# ptvo_fs.net
KiCad netlist of a schematic drawn in EAGLE
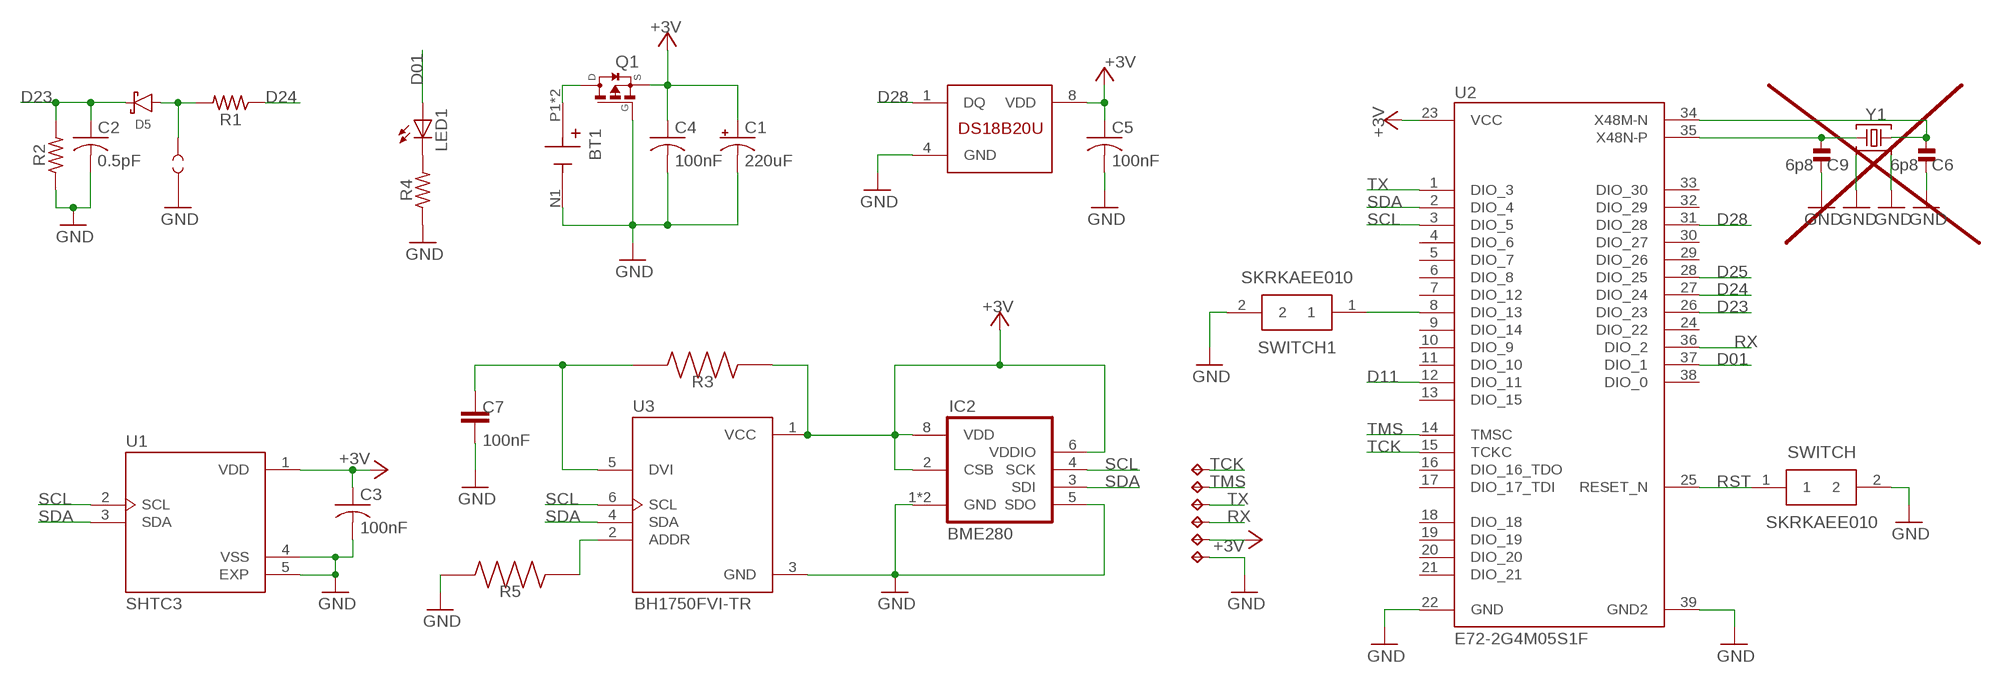
[diagram p0: schematic, sheet 1]

(export (version "E")
  (design (tool "Eeschema 10.0.6"))
  (components
    (comp (ref "BT1")
      (value "BAT-HLD-001")
      (footprint "eagle-import:BAT_BAT-HLD-001")
      (libsource (lib "eagle-import") (part "BAT-HLD-001"))
    )
    (comp (ref "C1")
      (value "220uF")
      (footprint "eagle-import:EIA7343")
      (libsource (lib "eagle-import") (part "100UF-POLAR-EIA7343-10V-10%(TANT)"))
    )
    (comp (ref "C2")
      (value "0.5pF")
      (footprint "eagle-import:C0805")
      (libsource (lib "eagle-import") (part "C-USC0805"))
    )
    (comp (ref "C3")
      (value "100nF")
      (footprint "eagle-import:C0805")
      (libsource (lib "eagle-import") (part "C-USC0805"))
    )
    (comp (ref "C4")
      (value "100nF")
      (footprint "eagle-import:C0805")
      (libsource (lib "eagle-import") (part "C-USC0805"))
    )
    (comp (ref "C5")
      (value "100nF")
      (footprint "eagle-import:C0805")
      (libsource (lib "eagle-import") (part "C-USC0805"))
    )
    (comp (ref "C6")
      (value "6p8")
      (footprint "eagle-import:_PKG_C_0402")
      (libsource (lib "eagle-import") (part "CAP-0402"))
    )
    (comp (ref "C7")
      (value "100nF")
      (footprint "eagle-import:CAPC1005X40N")
      (fields (field (name "MF") "Yageo") (field (name "MP") "RC0402FR-073M6L"))
      (libsource (lib "eagle-import") (part "CAP0402"))
    )
    (comp (ref "C9")
      (value "6p8")
      (footprint "eagle-import:_PKG_C_0402")
      (libsource (lib "eagle-import") (part "CAP-0402"))
    )
    (comp (ref "D5")
      (value "1N4148WS")
      (footprint "eagle-import:SOD-323")
      (libsource (lib "eagle-import") (part "DIODE-SCHOTTKY"))
    )
    (comp (ref "IC1")
      (value "DS18S20USOP8")
      (footprint "eagle-import:UMAX8")
      (libsource (lib "eagle-import") (part "DS18S20USOP8"))
    )
    (comp (ref "IC2")
      (value "BME280")
      (footprint "eagle-import:BME280")
      (libsource (lib "eagle-import") (part "BME280"))
    )
    (comp (ref "LED1")
      (value "LEDCHIP-LED0805")
      (footprint "eagle-import:CHIP-LED0805")
      (libsource (lib "eagle-import") (part "LEDCHIP-LED0805"))
    )
    (comp (ref "Q1")
      (value "SI2323DS")
      (footprint "eagle-import:SOT23")
      (fields (field (name "MF") "Vishay Siliconix"))
      (libsource (lib "eagle-import") (part "SI2323DS"))
    )
    (comp (ref "R1")
      (value "10k")
      (footprint "eagle-import:M0805")
      (libsource (lib "eagle-import") (part "R-US_M0805"))
    )
    (comp (ref "R2")
      (value "1M")
      (footprint "eagle-import:M0805")
      (libsource (lib "eagle-import") (part "R-US_M0805"))
    )
    (comp (ref "R3")
      (value "4.7k")
      (footprint "eagle-import:RESC1005X40N")
      (fields (field (name "MF") "Yageo") (field (name "MP") "RC0402FR-073M6L"))
      (libsource (lib "eagle-import") (part "RC0402FR-073M6L"))
    )
    (comp (ref "R4")
      (value "2.2k")
      (footprint "eagle-import:M0805")
      (libsource (lib "eagle-import") (part "R-US_M0805"))
    )
    (comp (ref "R5")
      (value "4.7k")
      (footprint "eagle-import:RESC1005X40N")
      (fields (field (name "MF") "Yageo") (field (name "MP") "RC0402FR-073M6L"))
      (libsource (lib "eagle-import") (part "RC0402FR-073M6L"))
    )
    (comp (ref "SWITCH")
      (value "SKRKAEE010")
      (footprint "eagle-import:SKRK")
      (fields (field (name "MF") "ALPS"))
      (libsource (lib "eagle-import") (part "SKRKAEE010"))
    )
    (comp (ref "SWITCH1")
      (value "SKRKAEE010")
      (footprint "eagle-import:SKRK")
      (fields (field (name "MF") "ALPS"))
      (libsource (lib "eagle-import") (part "SKRKAEE010"))
    )
    (comp (ref "TP1")
      (value "TEST-POINT2")
      (footprint "eagle-import:PAD.02X.02")
      (libsource (lib "eagle-import") (part "TEST-POINT2"))
    )
    (comp (ref "TP2")
      (value "TEST-POINT2")
      (footprint "eagle-import:PAD.02X.02")
      (libsource (lib "eagle-import") (part "TEST-POINT2"))
    )
    (comp (ref "TP3")
      (value "TPB1,27")
      (footprint "eagle-import:B1,27")
      (libsource (lib "eagle-import") (part "TPB1,27"))
    )
    (comp (ref "TP4")
      (value "TPB1,27")
      (footprint "eagle-import:B1,27")
      (libsource (lib "eagle-import") (part "TPB1,27"))
    )
    (comp (ref "TP5")
      (value "TPB1,27")
      (footprint "eagle-import:B1,27")
      (libsource (lib "eagle-import") (part "TPB1,27"))
    )
    (comp (ref "TP6")
      (value "TPB1,27")
      (footprint "eagle-import:B1,27")
      (libsource (lib "eagle-import") (part "TPB1,27"))
    )
    (comp (ref "TP7")
      (value "TPB1,27")
      (footprint "eagle-import:B1,27")
      (libsource (lib "eagle-import") (part "TPB1,27"))
    )
    (comp (ref "TP8")
      (value "TPB1,27")
      (footprint "eagle-import:B1,27")
      (libsource (lib "eagle-import") (part "TPB1,27"))
    )
    (comp (ref "U1")
      (value "SHTC3")
      (footprint "eagle-import:SON100P200X200X80-5N")
      (fields (field (name "MF") "Sensirion AG"))
      (libsource (lib "eagle-import") (part "SHTC3"))
    )
    (comp (ref "U2")
      (value "E72-2G4M05S1F")
      (footprint "eagle-import:E72-2G4M05S1F")
      (libsource (lib "eagle-import") (part "E72-2G4M05S1F"))
    )
    (comp (ref "U3")
      (value "BH1750FVI-TR")
      (footprint "eagle-import:XDCR_BH1750FVI-TR")
      (fields (field (name "MF") "Rohm"))
      (libsource (lib "eagle-import") (part "BH1750FVI-TR"))
    )
    (comp (ref "Y1")
      (value "Q22FA12800150")
      (footprint "eagle-import:XTAL-4P-2016")
      (fields (field (name "DIGIKEY_PART") "1253-2042-1-ND") (field (name "MFG_PART") "CX2016DB48000C0FPLC1"))
      (libsource (lib "eagle-import") (part "48.000MHZ_CX2016DB48000C0FPLC1"))
    )
  )
  (nets
    (net (code "1") (name "+3V") (class "Default")
      (node (ref "C1") (pin "A") (pinfunction "+_A") (pintype "passive"))
      (node (ref "C3") (pin "1") (pinfunction "1_1") (pintype "passive"))
      (node (ref "C4") (pin "1") (pinfunction "1_1") (pintype "passive"))
      (node (ref "C5") (pin "1") (pinfunction "1_1") (pintype "passive"))
      (node (ref "IC1") (pin "8") (pinfunction "VDD_8") (pintype "power_in"))
      (node (ref "IC2") (pin "2") (pinfunction "CSB_2") (pintype "input"))
      (node (ref "IC2") (pin "6") (pinfunction "VDDIO_6") (pintype "power_in"))
      (node (ref "IC2") (pin "8") (pinfunction "VDD_8") (pintype "power_in"))
      (node (ref "Q1") (pin "2") (pinfunction "S_2") (pintype "passive"))
      (node (ref "R3") (pin "1") (pinfunction "1_1") (pintype "passive"))
      (node (ref "TP6") (pin "TP") (pinfunction "TP_TP") (pintype "input"))
      (node (ref "U1") (pin "1") (pinfunction "VDD_1") (pintype "power_in"))
      (node (ref "U2") (pin "23") (pinfunction "VCC_23") (pintype "bidirectional"))
      (node (ref "U3") (pin "1") (pinfunction "VCC_1") (pintype "power_in"))
    )
    (net (code "2") (name "/D01") (class "Default")
      (node (ref "LED1") (pin "A") (pinfunction "A_A") (pintype "passive"))
      (node (ref "U2") (pin "37") (pinfunction "DIO_1_37") (pintype "bidirectional"))
    )
    (net (code "3") (name "/D11") (class "Default")
      (node (ref "U2") (pin "12") (pinfunction "DIO_11_12") (pintype "bidirectional"))
    )
    (net (code "4") (name "/D23") (class "Default")
      (node (ref "C2") (pin "1") (pinfunction "1_1") (pintype "passive"))
      (node (ref "D5") (pin "C") (pinfunction "C_C") (pintype "passive"))
      (node (ref "R2") (pin "2") (pinfunction "2_2") (pintype "passive"))
      (node (ref "U2") (pin "26") (pinfunction "DIO_23_26") (pintype "bidirectional"))
    )
    (net (code "5") (name "/D24") (class "Default")
      (node (ref "R1") (pin "1") (pinfunction "1_1") (pintype "passive"))
      (node (ref "U2") (pin "27") (pinfunction "DIO_24_27") (pintype "bidirectional"))
    )
    (net (code "6") (name "/D25") (class "Default")
      (node (ref "U2") (pin "28") (pinfunction "DIO_25_28") (pintype "bidirectional"))
    )
    (net (code "7") (name "/D28") (class "Default")
      (node (ref "IC1") (pin "1") (pinfunction "DQ_1") (pintype "bidirectional"))
      (node (ref "U2") (pin "31") (pinfunction "DIO_28_31") (pintype "bidirectional"))
    )
    (net (code "8") (name "/RST") (class "Default")
      (node (ref "SWITCH") (pin "1") (pinfunction "1_1") (pintype "passive"))
      (node (ref "U2") (pin "25") (pinfunction "RESET_N_25") (pintype "bidirectional"))
    )
    (net (code "9") (name "/RX") (class "Default")
      (node (ref "TP5") (pin "TP") (pinfunction "TP_TP") (pintype "input"))
      (node (ref "U2") (pin "36") (pinfunction "DIO_2_36") (pintype "bidirectional"))
    )
    (net (code "10") (name "/SCL") (class "Default")
      (node (ref "IC2") (pin "4") (pinfunction "SCK_4") (pintype "bidirectional"))
      (node (ref "U1") (pin "2") (pinfunction "SCL_2") (pintype "bidirectional"))
      (node (ref "U2") (pin "3") (pinfunction "DIO_5_3") (pintype "bidirectional"))
      (node (ref "U3") (pin "6") (pinfunction "SCL_6") (pintype "input"))
    )
    (net (code "11") (name "/SDA") (class "Default")
      (node (ref "IC2") (pin "3") (pinfunction "SDI_3") (pintype "bidirectional"))
      (node (ref "U1") (pin "3") (pinfunction "SDA_3") (pintype "bidirectional"))
      (node (ref "U2") (pin "2") (pinfunction "DIO_4_2") (pintype "bidirectional"))
      (node (ref "U3") (pin "4") (pinfunction "SDA_4") (pintype "bidirectional"))
    )
    (net (code "12") (name "/TCK") (class "Default")
      (node (ref "TP8") (pin "TP") (pinfunction "TP_TP") (pintype "input"))
      (node (ref "U2") (pin "15") (pinfunction "TCKC_15") (pintype "bidirectional"))
    )
    (net (code "13") (name "/TMS") (class "Default")
      (node (ref "TP3") (pin "TP") (pinfunction "TP_TP") (pintype "input"))
      (node (ref "U2") (pin "14") (pinfunction "TMSC_14") (pintype "bidirectional"))
    )
    (net (code "14") (name "/TX") (class "Default")
      (node (ref "TP4") (pin "TP") (pinfunction "TP_TP") (pintype "input"))
      (node (ref "U2") (pin "1") (pinfunction "DIO_3_1") (pintype "bidirectional"))
    )
    (net (code "15") (name "GND") (class "Default")
      (node (ref "BT1") (pin "N1") (pinfunction "-_N1") (pintype "passive"))
      (node (ref "C1") (pin "C") (pinfunction "-_C") (pintype "passive"))
      (node (ref "C2") (pin "2") (pinfunction "2_2") (pintype "passive"))
      (node (ref "C3") (pin "2") (pinfunction "2_2") (pintype "passive"))
      (node (ref "C4") (pin "2") (pinfunction "2_2") (pintype "passive"))
      (node (ref "C5") (pin "2") (pinfunction "2_2") (pintype "passive"))
      (node (ref "C6") (pin "1") (pinfunction "1_1") (pintype "passive"))
      (node (ref "C7") (pin "2") (pinfunction "2_2") (pintype "passive"))
      (node (ref "C9") (pin "1") (pinfunction "1_1") (pintype "passive"))
      (node (ref "IC1") (pin "4") (pinfunction "GND_4") (pintype "power_in"))
      (node (ref "IC2") (pin "1") (pinfunction "GND_1") (pintype "power_in"))
      (node (ref "IC2") (pin "5") (pinfunction "SDO_5") (pintype "input"))
      (node (ref "IC2") (pin "7") (pinfunction "GND_7") (pintype "power_in"))
      (node (ref "Q1") (pin "1") (pinfunction "G_1") (pintype "passive"))
      (node (ref "R2") (pin "1") (pinfunction "1_1") (pintype "passive"))
      (node (ref "R4") (pin "1") (pinfunction "1_1") (pintype "passive"))
      (node (ref "R5") (pin "2") (pinfunction "2_2") (pintype "passive"))
      (node (ref "SWITCH") (pin "2") (pinfunction "2_2") (pintype "passive"))
      (node (ref "SWITCH1") (pin "2") (pinfunction "2_2") (pintype "passive"))
      (node (ref "TP2") (pin "P$1") (pinfunction "1_P$1") (pintype "bidirectional"))
      (node (ref "TP7") (pin "TP") (pinfunction "TP_TP") (pintype "input"))
      (node (ref "U1") (pin "4") (pinfunction "VSS_4") (pintype "power_in"))
      (node (ref "U1") (pin "5") (pinfunction "EXP_5") (pintype "power_in"))
      (node (ref "U2") (pin "22") (pinfunction "GND_22") (pintype "bidirectional"))
      (node (ref "U2") (pin "39") (pinfunction "GND2_39") (pintype "bidirectional"))
      (node (ref "U3") (pin "3") (pinfunction "GND_3") (pintype "power_in"))
      (node (ref "Y1") (pin "2") (pinfunction "2_2") (pintype "bidirectional"))
      (node (ref "Y1") (pin "4") (pinfunction "4_4") (pintype "bidirectional"))
    )
    (net (code "16") (name "Net-(LED1-PadC)") (class "Default")
      (node (ref "LED1") (pin "C") (pinfunction "C_C") (pintype "passive"))
      (node (ref "R4") (pin "2") (pinfunction "2_2") (pintype "passive"))
    )
    (net (code "17") (name "Net-(Q1-D)") (class "Default")
      (node (ref "BT1") (pin "P1") (pinfunction "+_P1") (pintype "passive"))
      (node (ref "BT1") (pin "P2") (pinfunction "+_P2") (pintype "passive"))
      (node (ref "Q1") (pin "3") (pinfunction "D_3") (pintype "passive"))
    )
    (net (code "18") (name "Net-(TP1-1)") (class "Default")
      (node (ref "D5") (pin "A") (pinfunction "A_A") (pintype "passive"))
      (node (ref "R1") (pin "2") (pinfunction "2_2") (pintype "passive"))
      (node (ref "TP1") (pin "P$1") (pinfunction "1_P$1") (pintype "bidirectional"))
    )
    (net (code "19") (name "Net-(U2-DIO_13)") (class "Default")
      (node (ref "SWITCH1") (pin "1") (pinfunction "1_1") (pintype "passive"))
      (node (ref "U2") (pin "8") (pinfunction "DIO_13_8") (pintype "bidirectional"))
    )
    (net (code "20") (name "Net-(U2-X48M-N)") (class "Default")
      (node (ref "C6") (pin "2") (pinfunction "2_2") (pintype "passive"))
      (node (ref "U2") (pin "34") (pinfunction "X48M-N_34") (pintype "bidirectional"))
      (node (ref "Y1") (pin "3") (pinfunction "3_3") (pintype "passive"))
    )
    (net (code "21") (name "Net-(U2-X48N-P)") (class "Default")
      (node (ref "C9") (pin "2") (pinfunction "2_2") (pintype "passive"))
      (node (ref "U2") (pin "35") (pinfunction "X48N-P_35") (pintype "bidirectional"))
      (node (ref "Y1") (pin "1") (pinfunction "1_1") (pintype "passive"))
    )
    (net (code "22") (name "Net-(U3-ADDR)") (class "Default")
      (node (ref "R5") (pin "1") (pinfunction "1_1") (pintype "passive"))
      (node (ref "U3") (pin "2") (pinfunction "ADDR_2") (pintype "input"))
    )
    (net (code "23") (name "Net-(U3-DVI)") (class "Default")
      (node (ref "C7") (pin "1") (pinfunction "1_1") (pintype "passive"))
      (node (ref "R3") (pin "2") (pinfunction "2_2") (pintype "passive"))
      (node (ref "U3") (pin "5") (pinfunction "DVI_5") (pintype "input"))
    )
    (net (code "24") (name "unconnected-(U2-DIO_0-Pad38)") (class "Default")
      (node (ref "U2") (pin "38") (pinfunction "DIO_0_38") (pintype "bidirectional"))
    )
    (net (code "25") (name "unconnected-(U2-DIO_6-Pad4)") (class "Default")
      (node (ref "U2") (pin "4") (pinfunction "DIO_6_4") (pintype "bidirectional"))
    )
    (net (code "26") (name "unconnected-(U2-DIO_7-Pad5)") (class "Default")
      (node (ref "U2") (pin "5") (pinfunction "DIO_7_5") (pintype "bidirectional"))
    )
    (net (code "27") (name "unconnected-(U2-DIO_8-Pad6)") (class "Default")
      (node (ref "U2") (pin "6") (pinfunction "DIO_8_6") (pintype "bidirectional"))
    )
    (net (code "28") (name "unconnected-(U2-DIO_9-Pad10)") (class "Default")
      (node (ref "U2") (pin "10") (pinfunction "DIO_9_10") (pintype "bidirectional"))
    )
    (net (code "29") (name "unconnected-(U2-DIO_10-Pad11)") (class "Default")
      (node (ref "U2") (pin "11") (pinfunction "DIO_10_11") (pintype "bidirectional"))
    )
    (net (code "30") (name "unconnected-(U2-DIO_12-Pad7)") (class "Default")
      (node (ref "U2") (pin "7") (pinfunction "DIO_12_7") (pintype "bidirectional"))
    )
    (net (code "31") (name "unconnected-(U2-DIO_14-Pad9)") (class "Default")
      (node (ref "U2") (pin "9") (pinfunction "DIO_14_9") (pintype "bidirectional"))
    )
    (net (code "32") (name "unconnected-(U2-DIO_15-Pad13)") (class "Default")
      (node (ref "U2") (pin "13") (pinfunction "DIO_15_13") (pintype "bidirectional"))
    )
    (net (code "33") (name "unconnected-(U2-DIO_16_TDO-Pad16)") (class "Default")
      (node (ref "U2") (pin "16") (pinfunction "DIO_16_TDO_16") (pintype "bidirectional"))
    )
    (net (code "34") (name "unconnected-(U2-DIO_17_TDI-Pad17)") (class "Default")
      (node (ref "U2") (pin "17") (pinfunction "DIO_17_TDI_17") (pintype "bidirectional"))
    )
    (net (code "35") (name "unconnected-(U2-DIO_18-Pad18)") (class "Default")
      (node (ref "U2") (pin "18") (pinfunction "DIO_18_18") (pintype "bidirectional"))
    )
    (net (code "36") (name "unconnected-(U2-DIO_19-Pad19)") (class "Default")
      (node (ref "U2") (pin "19") (pinfunction "DIO_19_19") (pintype "bidirectional"))
    )
    (net (code "37") (name "unconnected-(U2-DIO_20-Pad20)") (class "Default")
      (node (ref "U2") (pin "20") (pinfunction "DIO_20_20") (pintype "bidirectional"))
    )
    (net (code "38") (name "unconnected-(U2-DIO_21-Pad21)") (class "Default")
      (node (ref "U2") (pin "21") (pinfunction "DIO_21_21") (pintype "bidirectional"))
    )
    (net (code "39") (name "unconnected-(U2-DIO_22-Pad24)") (class "Default")
      (node (ref "U2") (pin "24") (pinfunction "DIO_22_24") (pintype "bidirectional"))
    )
    (net (code "40") (name "unconnected-(U2-DIO_26-Pad29)") (class "Default")
      (node (ref "U2") (pin "29") (pinfunction "DIO_26_29") (pintype "bidirectional"))
    )
    (net (code "41") (name "unconnected-(U2-DIO_27-Pad30)") (class "Default")
      (node (ref "U2") (pin "30") (pinfunction "DIO_27_30") (pintype "bidirectional"))
    )
    (net (code "42") (name "unconnected-(U2-DIO_29-Pad32)") (class "Default")
      (node (ref "U2") (pin "32") (pinfunction "DIO_29_32") (pintype "bidirectional"))
    )
    (net (code "43") (name "unconnected-(U2-DIO_30-Pad33)") (class "Default")
      (node (ref "U2") (pin "33") (pinfunction "DIO_30_33") (pintype "bidirectional"))
    )
  )
)
